# Sheet1.net
KiCad netlist of a schematic drawn in Altium Designer
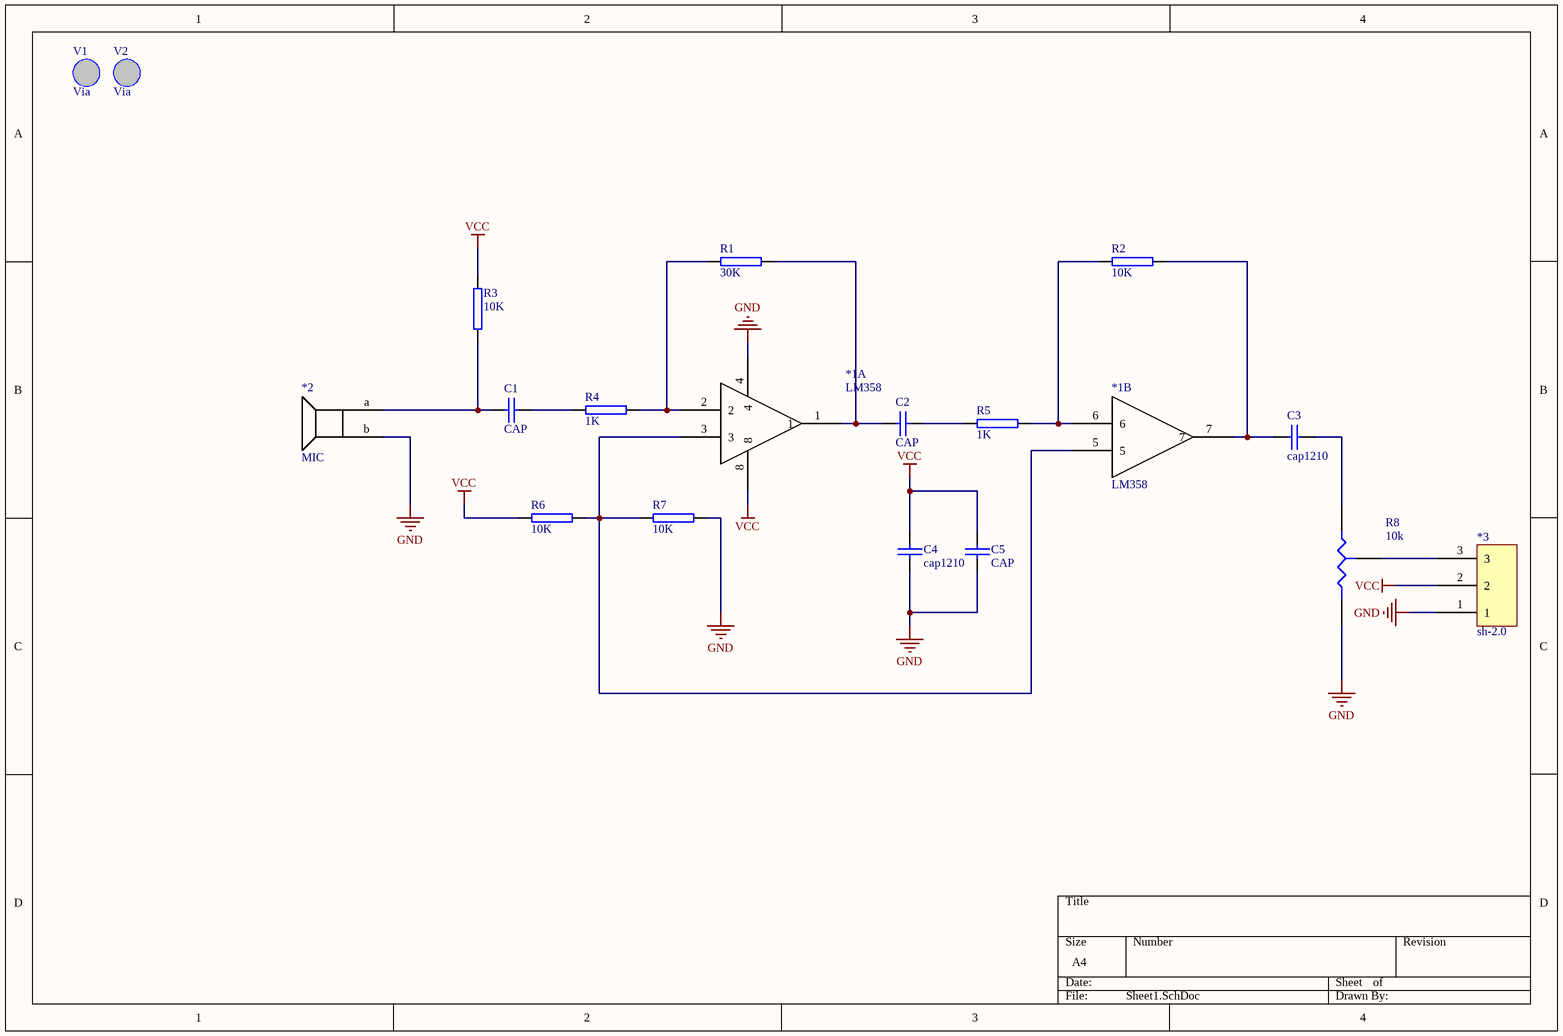
[diagram p0: Sheet1.SchDoc]

(export (version "E")
  (design (tool "Eeschema 10.0.6"))
  (components
    (comp (ref "*1") (value "LM358") (footprint "HMC_S8") (libsource (lib "zhangchong") (part "LM358")))
    (comp (ref "*2") (value "MIC") (libsource (lib "zhangchong") (part "MIC")))
    (comp (ref "*3") (value "sh-2.0") (footprint "sh-2.0") (libsource (lib "zhangchong") (part "sh-2.0")))
    (comp (ref "C1")
      (value "CAP")
      (footprint "Miscellaneous Devices:1608[0603]")
      (libsource (lib "gupeng_sch") (part "CAP"))
    )
    (comp (ref "C2")
      (value "CAP")
      (footprint "Miscellaneous Devices:1608[0603]")
      (libsource (lib "gupeng_sch") (part "CAP"))
    )
    (comp (ref "C3")
      (value "cap1210")
      (footprint "Miscellaneous Devices:C1210")
      (libsource (lib "PEI_SCH") (part "cap0603"))
    )
    (comp (ref "C4")
      (value "cap1210")
      (footprint "Miscellaneous Devices:C1210")
      (libsource (lib "PEI_SCH") (part "cap0603"))
    )
    (comp (ref "C5") (value "CAP") (footprint "gupeng_pcb:0402") (libsource (lib "gupeng_sch") (part "CAP")))
    (comp (ref "R1")
      (value "30K")
      (footprint "Miscellaneous Devices:1608[0603]")
      (libsource (lib "gupeng_sch") (part "RES"))
    )
    (comp (ref "R2")
      (value "10K")
      (footprint "Miscellaneous Devices:1608[0603]")
      (libsource (lib "gupeng_sch") (part "RES"))
    )
    (comp (ref "R3")
      (value "10K")
      (footprint "Miscellaneous Devices:1608[0603]")
      (libsource (lib "gupeng_sch") (part "RES"))
    )
    (comp (ref "R4")
      (value "1K")
      (footprint "Miscellaneous Devices:1608[0603]")
      (libsource (lib "gupeng_sch") (part "RES"))
    )
    (comp (ref "R5")
      (value "1K")
      (footprint "Miscellaneous Devices:1608[0603]")
      (libsource (lib "gupeng_sch") (part "RES"))
    )
    (comp (ref "R6")
      (value "10K")
      (footprint "Miscellaneous Devices:1608[0603]")
      (libsource (lib "gupeng_sch") (part "RES"))
    )
    (comp (ref "R7")
      (value "10K")
      (footprint "Miscellaneous Devices:1608[0603]")
      (libsource (lib "gupeng_sch") (part "RES"))
    )
    (comp (ref "R8")
      (value "10k")
      (footprint "BORUNS_3314J-1")
      (libsource (lib "gupeng_sch") (part "Res Tap"))
    )
    (comp (ref "V1") (value "Via") (footprint "zhangchong:Via") (libsource (lib "zhangchong") (part "Via")))
    (comp (ref "V2") (value "Via") (footprint "zhangchong:Via") (libsource (lib "zhangchong") (part "Via")))
  )
  (nets
    (net (code "1") (name "GND") (class "Default")
      (node (ref "*1") (pin "4") (pinfunction "4_4") (pintype "passive"))
      (node (ref "*3") (pin "1") (pinfunction "1_1") (pintype "passive"))
      (node (ref "C4") (pin "2") (pinfunction "2_2") (pintype "passive"))
      (node (ref "C5") (pin "1") (pinfunction "1_1") (pintype "passive"))
      (node (ref "R7") (pin "2") (pinfunction "2_2") (pintype "passive"))
      (node (ref "R8") (pin "2") (pinfunction "B_2") (pintype "passive"))
    )
    (net (code "2") (name "Net-(*1-Pad1)") (class "Default")
      (node (ref "*1") (pin "1") (pinfunction "1_1") (pintype "passive"))
      (node (ref "C2") (pin "1") (pinfunction "1_1") (pintype "passive"))
      (node (ref "R1") (pin "2") (pinfunction "2_2") (pintype "passive"))
    )
    (net (code "3") (name "Net-(*1-Pad2)") (class "Default")
      (node (ref "*1") (pin "2") (pinfunction "2_2") (pintype "passive"))
      (node (ref "R1") (pin "1") (pinfunction "1_1") (pintype "passive"))
      (node (ref "R4") (pin "2") (pinfunction "2_2") (pintype "passive"))
    )
    (net (code "4") (name "Net-(*1-Pad3)") (class "Default")
      (node (ref "*1") (pin "3") (pinfunction "3_3") (pintype "passive"))
      (node (ref "*1") (pin "5") (pinfunction "5_5") (pintype "passive"))
      (node (ref "R6") (pin "2") (pinfunction "2_2") (pintype "passive"))
      (node (ref "R7") (pin "1") (pinfunction "1_1") (pintype "passive"))
    )
    (net (code "5") (name "Net-(*1-Pad6)") (class "Default")
      (node (ref "*1") (pin "6") (pinfunction "6_6") (pintype "passive"))
      (node (ref "R2") (pin "1") (pinfunction "1_1") (pintype "passive"))
      (node (ref "R5") (pin "2") (pinfunction "2_2") (pintype "passive"))
    )
    (net (code "6") (name "Net-(*1-Pad7)") (class "Default")
      (node (ref "*1") (pin "7") (pinfunction "7_7") (pintype "passive"))
      (node (ref "C3") (pin "1") (pinfunction "1_1") (pintype "passive"))
      (node (ref "R2") (pin "2") (pinfunction "2_2") (pintype "passive"))
    )
    (net (code "7") (name "Net-(C1-Pad1)") (class "Default")
      (node (ref "C1") (pin "1") (pinfunction "1_1") (pintype "passive"))
      (node (ref "R3") (pin "1") (pinfunction "1_1") (pintype "passive"))
    )
    (net (code "8") (name "Net-(C1-Pad2)") (class "Default")
      (node (ref "C1") (pin "2") (pinfunction "2_2") (pintype "passive"))
      (node (ref "R4") (pin "1") (pinfunction "1_1") (pintype "passive"))
    )
    (net (code "9") (name "Net-(C2-Pad2)") (class "Default")
      (node (ref "C2") (pin "2") (pinfunction "2_2") (pintype "passive"))
      (node (ref "R5") (pin "1") (pinfunction "1_1") (pintype "passive"))
    )
    (net (code "10") (name "Net-(R8-A)") (class "Default")
      (node (ref "C3") (pin "2") (pinfunction "2_2") (pintype "passive"))
      (node (ref "R8") (pin "1") (pinfunction "A_1") (pintype "passive"))
    )
    (net (code "11") (name "Net-(R8-TAP)") (class "Default")
      (node (ref "*3") (pin "3") (pinfunction "3_3") (pintype "passive"))
      (node (ref "R8") (pin "3") (pinfunction "TAP_3") (pintype "passive"))
    )
    (net (code "12") (name "VCC") (class "Default")
      (node (ref "*1") (pin "8") (pinfunction "8_8") (pintype "passive"))
      (node (ref "*3") (pin "2") (pinfunction "2_2") (pintype "passive"))
      (node (ref "C4") (pin "1") (pinfunction "1_1") (pintype "passive"))
      (node (ref "C5") (pin "2") (pinfunction "2_2") (pintype "passive"))
      (node (ref "R3") (pin "2") (pinfunction "2_2") (pintype "passive"))
      (node (ref "R6") (pin "1") (pinfunction "1_1") (pintype "passive"))
    )
    (net (code "13") (name "unconnected-(*2-1-Pada)") (class "Default")
      (node (ref "*2") (pin "a") (pinfunction "1_a") (pintype "passive"))
    )
    (net (code "14") (name "unconnected-(*2-2-Padb)") (class "Default")
      (node (ref "*2") (pin "b") (pinfunction "2_b") (pintype "passive"))
    )
  )
)
